# rs485.net
KiCad netlist of a schematic drawn in Altium Designer
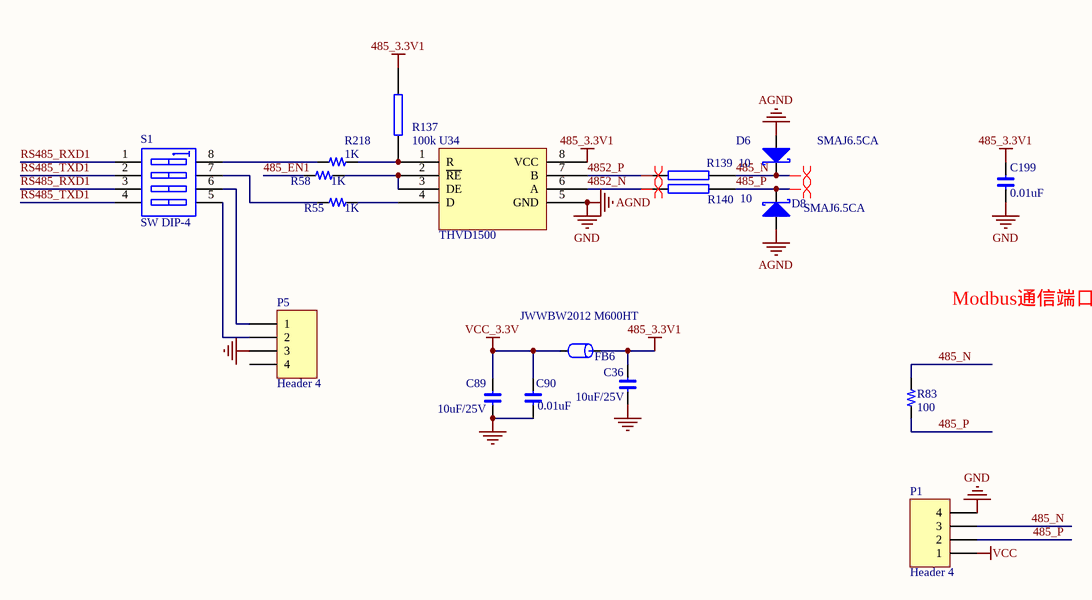
[diagram p0: rs485.SchDoc]

(export (version "E")
  (design (tool "Eeschema 10.0.6"))
  (components
    (comp (ref "C36")
      (value "10uF/25V")
      (footprint "0603C")
      (description "C")
      (libsource (lib "Schlib_20110825") (part "C"))
    )
    (comp (ref "C89")
      (value "10uF/25V")
      (footprint "0603C")
      (description "C")
      (libsource (lib "Schlib_20110825") (part "C"))
    )
    (comp (ref "C90")
      (value "0.01uF")
      (footprint "0603C")
      (description "C")
      (libsource (lib "Schlib_20110825") (part "C"))
    )
    (comp (ref "C199")
      (value "0.01uF")
      (footprint "0603C")
      (description "C")
      (libsource (lib "Schlib_20110825") (part "C"))
    )
    (comp (ref "D6")
      (value "SMAJ6.5CA")
      (footprint "SMA")
      (description "Schottky Diode")
      (libsource (lib "*") (part "DIODE S"))
    )
    (comp (ref "D8")
      (value "SMAJ6.5CA")
      (footprint "SMA")
      (description "Schottky Diode")
      (libsource (lib "*") (part "DIODE S"))
    )
    (comp (ref "FB6")
      (value "JWWBW2012 M600HT")
      (footprint "0805CZ")
      (libsource (lib "Schlib_20110825") (part "FB"))
    )
    (comp (ref "P1")
      (value "Header 4")
      (footprint "4X2.54MMZ")
      (description "Header, 4-Pin")
      (fields (field (name "PUBLISHER") "Altium Limited"))
      (libsource (lib "Miscellaneous Connectors") (part "Header 4"))
    )
    (comp (ref "P5")
      (value "Header 4")
      (footprint "4X2.54MMZ")
      (description "Header, 4-Pin")
      (fields (field (name "PUBLISHER") "Altium Limited"))
      (libsource (lib "") (part "Header 4_1"))
    )
    (comp (ref "R55") (value "1K") (footprint "0603R") (description "R") (libsource (lib "JRJ_1") (part "R")))
    (comp (ref "R58") (value "1K") (footprint "0603R") (description "R") (libsource (lib "JRJ_1") (part "R")))
    (comp (ref "R83")
      (value "100")
      (footprint "0603R")
      (description "R")
      (libsource (lib "JRJ_1") (part "R"))
    )
    (comp (ref "R137") (value "100k") (footprint "0603R") (libsource (lib "*") (part "RES2")))
    (comp (ref "R139") (value "10") (footprint "1206R") (libsource (lib "*") (part "RES2")))
    (comp (ref "R140") (value "10") (footprint "1206R") (libsource (lib "*") (part "RES2")))
    (comp (ref "R218")
      (value "1K")
      (footprint "0603R")
      (description "R")
      (libsource (lib "JRJ_1") (part "R"))
    )
    (comp (ref "S1")
      (value "SW DIP-4")
      (footprint "SW_SMT_8")
      (description "DIP Switch, 4 Position, SPST")
      (fields (field (name "PUBLISHER") "Altium Limited"))
      (libsource (lib "Miscellaneous Devices") (part "SW DIP-4"))
    )
    (comp (ref "U34") (value "THVD1500") (footprint "so-8") (libsource (lib "Schlib1") (part "SN65HVD06D")))
  )
  (nets
    (net (code "1") (name "/485_EN1") (class "Default") (node (ref "R58") (pin "2") (pintype "passive")))
    (net (code "2") (name "/485_N") (class "Default")
      (node (ref "D6") (pin "2") (pinfunction "K_2") (pintype "passive"))
      (node (ref "P1") (pin "3") (pinfunction "3_3") (pintype "passive"))
      (node (ref "R139") (pin "1") (pinfunction "1_1") (pintype "passive"))
      (node (ref "R83") (pin "2") (pintype "passive"))
    )
    (net (code "3") (name "/485_P") (class "Default")
      (node (ref "D8") (pin "2") (pinfunction "K_2") (pintype "passive"))
      (node (ref "P1") (pin "2") (pinfunction "2_2") (pintype "passive"))
      (node (ref "R140") (pin "1") (pinfunction "1_1") (pintype "passive"))
      (node (ref "R83") (pin "1") (pintype "passive"))
    )
    (net (code "4") (name "/4852_N") (class "Default")
      (node (ref "R140") (pin "2") (pinfunction "2_2") (pintype "passive"))
      (node (ref "U34") (pin "6") (pinfunction "A_6") (pintype "passive"))
    )
    (net (code "5") (name "/4852_P") (class "Default")
      (node (ref "R139") (pin "2") (pinfunction "2_2") (pintype "passive"))
      (node (ref "U34") (pin "7") (pinfunction "B_7") (pintype "passive"))
    )
    (net (code "6") (name "/RS485_RXD1") (class "Default")
      (node (ref "S1") (pin "1") (pinfunction "A1_1") (pintype "passive"))
      (node (ref "S1") (pin "3") (pinfunction "A3_3") (pintype "passive"))
    )
    (net (code "7") (name "/RS485_TXD1") (class "Default")
      (node (ref "S1") (pin "2") (pinfunction "A2_2") (pintype "passive"))
      (node (ref "S1") (pin "4") (pinfunction "A4_4") (pintype "passive"))
    )
    (net (code "8") (name "485_3.3V1") (class "Default")
      (node (ref "C199") (pin "2") (pintype "passive"))
      (node (ref "C36") (pin "2") (pintype "passive"))
      (node (ref "FB6") (pin "1") (pintype "passive"))
      (node (ref "R137") (pin "2") (pinfunction "2_2") (pintype "passive"))
      (node (ref "U34") (pin "8") (pinfunction "VCC_8") (pintype "passive"))
    )
    (net (code "9") (name "AGND") (class "Default")
      (node (ref "C199") (pin "1") (pintype "passive"))
      (node (ref "C36") (pin "1") (pintype "passive"))
      (node (ref "C89") (pin "1") (pintype "passive"))
      (node (ref "C90") (pin "1") (pintype "passive"))
      (node (ref "D6") (pin "1") (pinfunction "A_1") (pintype "passive"))
      (node (ref "D8") (pin "1") (pinfunction "A_1") (pintype "passive"))
      (node (ref "P1") (pin "4") (pinfunction "4_4") (pintype "passive"))
      (node (ref "P5") (pin "3") (pinfunction "3_3") (pintype "passive"))
      (node (ref "U34") (pin "5") (pinfunction "GND_5") (pintype "passive"))
    )
    (net (code "10") (name "Net-(S1-B1)") (class "Default")
      (node (ref "R218") (pin "2") (pintype "passive"))
      (node (ref "S1") (pin "8") (pinfunction "B1_8") (pintype "passive"))
    )
    (net (code "11") (name "Net-(S1-B2)") (class "Default")
      (node (ref "R55") (pin "2") (pintype "passive"))
      (node (ref "S1") (pin "7") (pinfunction "B2_7") (pintype "passive"))
    )
    (net (code "12") (name "Net-(S1-B3)") (class "Default")
      (node (ref "P5") (pin "1") (pinfunction "1_1") (pintype "passive"))
      (node (ref "S1") (pin "6") (pinfunction "B3_6") (pintype "passive"))
    )
    (net (code "13") (name "Net-(S1-B4)") (class "Default")
      (node (ref "P5") (pin "2") (pinfunction "2_2") (pintype "passive"))
      (node (ref "S1") (pin "5") (pinfunction "B4_5") (pintype "passive"))
    )
    (net (code "14") (name "Net-(U34-D)") (class "Default")
      (node (ref "R55") (pin "1") (pintype "passive"))
      (node (ref "U34") (pin "4") (pinfunction "D_4") (pintype "passive"))
    )
    (net (code "15") (name "Net-(U34-DE)") (class "Default")
      (node (ref "R58") (pin "1") (pintype "passive"))
      (node (ref "U34") (pin "2") (pinfunction "~{RE}_2") (pintype "passive"))
      (node (ref "U34") (pin "3") (pinfunction "DE_3") (pintype "passive"))
    )
    (net (code "16") (name "Net-(U34-R)") (class "Default")
      (node (ref "R137") (pin "1") (pinfunction "1_1") (pintype "passive"))
      (node (ref "R218") (pin "1") (pintype "passive"))
      (node (ref "U34") (pin "1") (pinfunction "R_1") (pintype "passive"))
    )
    (net (code "17") (name "VCC") (class "Default")
      (node (ref "P1") (pin "1") (pinfunction "1_1") (pintype "passive"))
    )
    (net (code "18") (name "VCC_3.3V") (class "Default")
      (node (ref "C89") (pin "2") (pintype "passive"))
      (node (ref "C90") (pin "2") (pintype "passive"))
      (node (ref "FB6") (pin "2") (pintype "passive"))
    )
    (net (code "19") (name "unconnected-(P5-Pad4)") (class "Default")
      (node (ref "P5") (pin "4") (pinfunction "4_4") (pintype "passive"))
    )
  )
)
